# LED_sch.net
KiCad netlist of a schematic drawn in Altium Designer
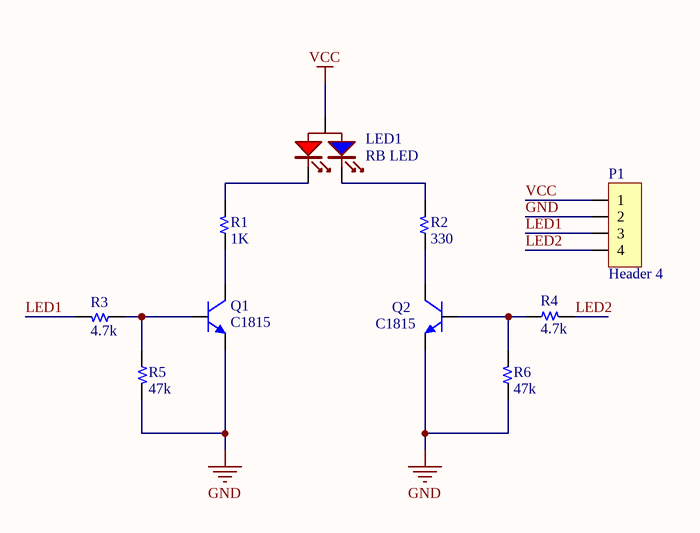
[diagram p0: LED_sch.SchDoc]

(export (version "E")
  (design (tool "Eeschema 10.0.6"))
  (components
    (comp (ref "LED1")
      (value "RB LED")
      (footprint "LED-BICOLOR-3MM")
      (description "Bicolor RB 3mm LED")
      (libsource (lib "led") (part "LED 2-color-A"))
    )
    (comp (ref "P1")
      (value "Header 4")
      (footprint "HDR/Header/4/BOX/RED")
      (description "Header, 4-Pin")
      (libsource (lib "connectors") (part "Header 4"))
    )
    (comp (ref "Q1")
      (value "C1815")
      (footprint "SOT-23")
      (description "NPN Bipolar Transistor")
      (libsource (lib "chipfc_libs") (part "Transistor NPN"))
    )
    (comp (ref "Q2")
      (value "C1815")
      (footprint "SOT-23")
      (description "NPN Bipolar Transistor")
      (libsource (lib "chipfc_libs") (part "Transistor NPN"))
    )
    (comp (ref "R1")
      (value "1K")
      (footprint "R 0603")
      (description "Resistor")
      (libsource (lib "chipfc_libs") (part "Resistor"))
    )
    (comp (ref "R2")
      (value "330")
      (footprint "R 0603")
      (description "Resistor")
      (libsource (lib "chipfc_libs") (part "Resistor"))
    )
    (comp (ref "R3")
      (value "4.7k")
      (footprint "R 0603")
      (description "Resistor")
      (libsource (lib "chipfc_libs") (part "Resistor"))
    )
    (comp (ref "R4")
      (value "4.7k")
      (footprint "R 0603")
      (description "Resistor")
      (libsource (lib "chipfc_libs") (part "Resistor"))
    )
    (comp (ref "R5")
      (value "47k")
      (footprint "R 0603")
      (description "Resistor")
      (libsource (lib "chipfc_libs") (part "Resistor"))
    )
    (comp (ref "R6")
      (value "47k")
      (footprint "R 0603")
      (description "Resistor")
      (libsource (lib "chipfc_libs") (part "Resistor"))
    )
  )
  (nets
    (net (code "1") (name "/LED1") (class "Default")
      (node (ref "P1") (pin "3") (pinfunction "3_3") (pintype "passive"))
      (node (ref "R3") (pin "2") (pinfunction "2_2") (pintype "passive"))
    )
    (net (code "2") (name "/LED2") (class "Default")
      (node (ref "P1") (pin "4") (pinfunction "4_4") (pintype "passive"))
      (node (ref "R4") (pin "2") (pinfunction "2_2") (pintype "passive"))
    )
    (net (code "3") (name "GND") (class "Default")
      (node (ref "P1") (pin "2") (pinfunction "2_2") (pintype "passive"))
      (node (ref "Q1") (pin "2") (pinfunction "E_2") (pintype "passive"))
      (node (ref "Q2") (pin "2") (pinfunction "E_2") (pintype "passive"))
      (node (ref "R5") (pin "2") (pinfunction "2_2") (pintype "passive"))
      (node (ref "R6") (pin "1") (pinfunction "1_1") (pintype "passive"))
    )
    (net (code "4") (name "Net-(LED1-K1)") (class "Default")
      (node (ref "LED1") (pin "1") (pinfunction "K1_1") (pintype "passive"))
      (node (ref "R1") (pin "2") (pinfunction "2_2") (pintype "passive"))
    )
    (net (code "5") (name "Net-(LED1-K2)") (class "Default")
      (node (ref "LED1") (pin "3") (pinfunction "K2_3") (pintype "passive"))
      (node (ref "R2") (pin "2") (pinfunction "2_2") (pintype "passive"))
    )
    (net (code "6") (name "Net-(Q1-B)") (class "Default")
      (node (ref "Q1") (pin "1") (pinfunction "B_1") (pintype "passive"))
      (node (ref "R3") (pin "1") (pinfunction "1_1") (pintype "passive"))
      (node (ref "R5") (pin "1") (pinfunction "1_1") (pintype "passive"))
    )
    (net (code "7") (name "Net-(Q1-C)") (class "Default")
      (node (ref "Q1") (pin "3") (pinfunction "C_3") (pintype "passive"))
      (node (ref "R1") (pin "1") (pinfunction "1_1") (pintype "passive"))
    )
    (net (code "8") (name "Net-(Q2-B)") (class "Default")
      (node (ref "Q2") (pin "1") (pinfunction "B_1") (pintype "passive"))
      (node (ref "R4") (pin "1") (pinfunction "1_1") (pintype "passive"))
      (node (ref "R6") (pin "2") (pinfunction "2_2") (pintype "passive"))
    )
    (net (code "9") (name "Net-(Q2-C)") (class "Default")
      (node (ref "Q2") (pin "3") (pinfunction "C_3") (pintype "passive"))
      (node (ref "R2") (pin "1") (pinfunction "1_1") (pintype "passive"))
    )
    (net (code "10") (name "VCC") (class "Default")
      (node (ref "LED1") (pin "2") (pinfunction "A_2") (pintype "passive"))
      (node (ref "P1") (pin "1") (pinfunction "1_1") (pintype "passive"))
    )
  )
)
